# Esquematico_fonte_3_3V.net
KiCad netlist of a schematic drawn in Altium Designer
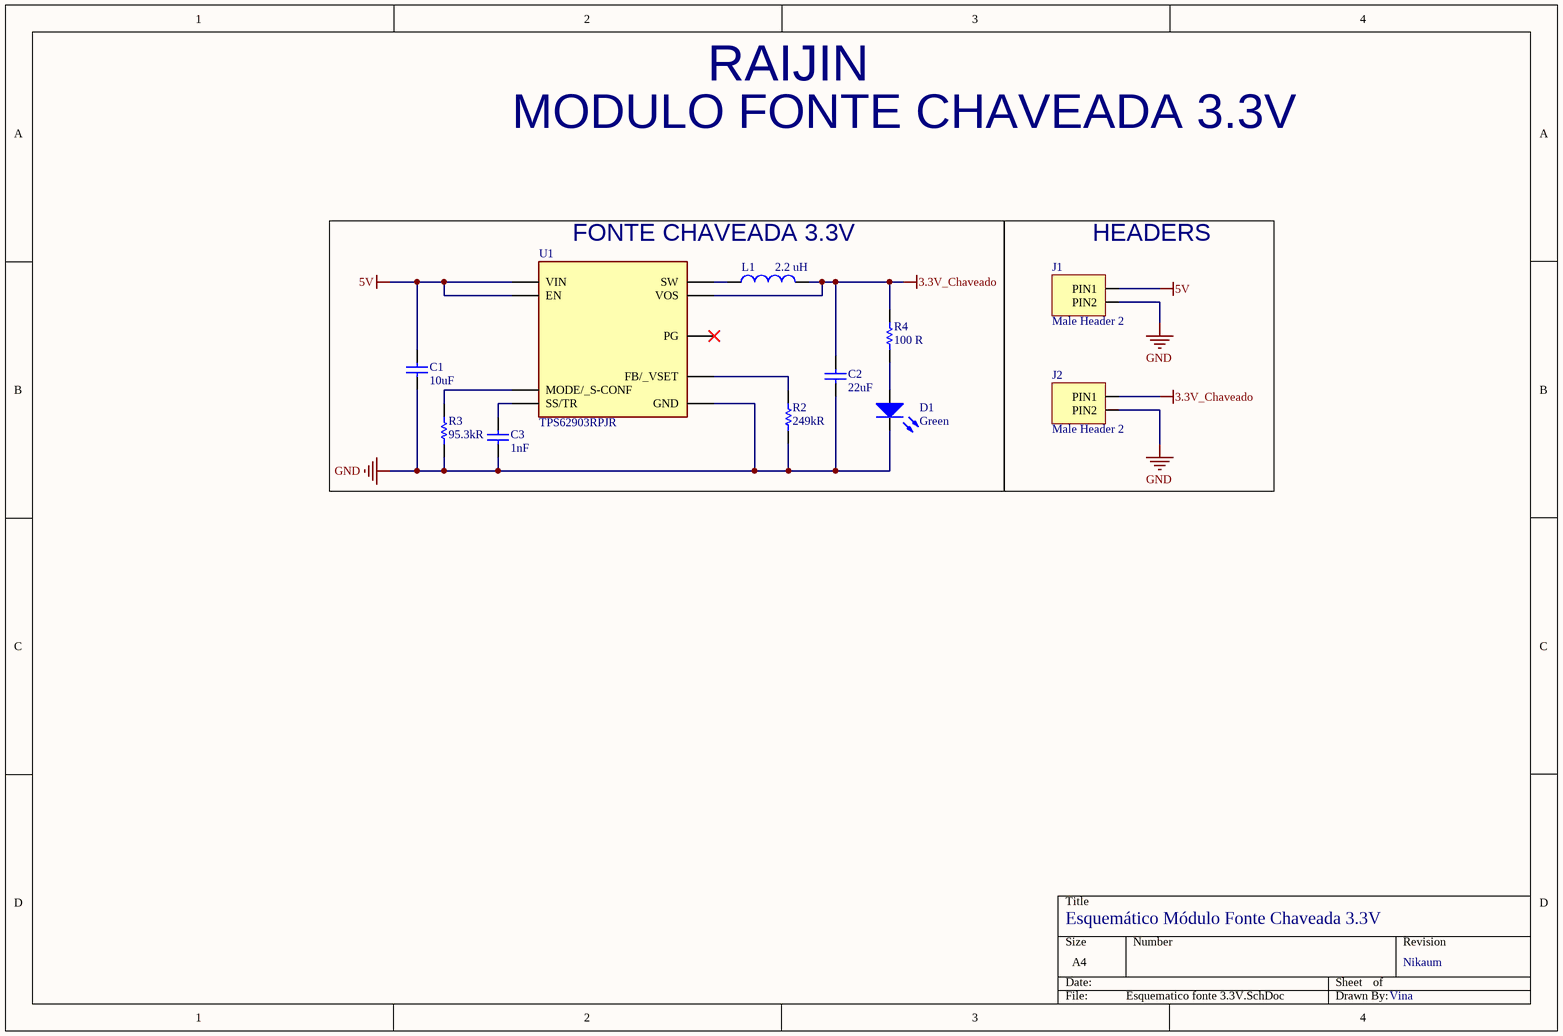
[diagram p0: Esquematico fonte 3.3V.SchDoc]

(export (version "E")
  (design (tool "Eeschema 10.0.6"))
  (components
    (comp (ref "C1")
      (value "10uF")
      (footprint "C0805")
      (description "CAP CER 10uF 10V 10% X5R 0805")
      (fields
        (field (name "MANUFACTURER") "KEMET")
        (field (name "PART NUMBER") "C0805C106K8PACTU")
        (field (name "LIBRARY CONTROL - PERSON THAT DID THE LAST UPDATE FOOTPRINT") "Marcos")
        (field (name "LIBRARY CONTROL - PERSON THAT DID THE LAST UPDATE SCHEMATIC") "Marcos")
      )
      (libsource (lib "Uai!Tecas") (part "C0805C106K8PACTU"))
    )
    (comp (ref "C2")
      (value "22uF")
      (footprint "C0603")
      (description "CAP TAN 22uF 6.3V 0603")
      (fields
        (field (name "MANUFACTURER") "AVX")
        (field (name "PART NUMBER") "F980J226MMA")
        (field (name "LIBRARY CONTROL - PERSON THAT CHECKED FOOTPRINT") "Nikaum")
        (field (name "LIBRARY CONTROL - PERSON THAT CHECKED SCHEMATIC") "Nikaum")
        (field (name "LIBRARY CONTROL - PERSON THAT DID THE LAST UPDATE FOOTPRINT") "Nikaum")
        (field (name "LIBRARY CONTROL - PERSON THAT DID THE LAST UPDATE SCHEMATIC") "Nikaum")
      )
      (libsource (lib "Uai!Tecas") (part "F980J226MMA"))
    )
    (comp (ref "C3")
      (value "1nF")
      (footprint "C0402")
      (description "CAP CER 1nF 10V 10% X5R 0402")
      (fields
        (field (name "MANUFACTURER") "Murata")
        (field (name "PART NUMBER") "GRM155R61A102KA01D")
        (field (name "LIBRARY CONTROL - PERSON THAT DID THE LAST UPDATE FOOTPRINT") "Marcos")
        (field (name "LIBRARY CONTROL - PERSON THAT DID THE LAST UPDATE SCHEMATIC") "Marcos")
      )
      (libsource (lib "Uai!Tecas") (part "GRM155R61A102KA01D"))
    )
    (comp (ref "D1")
      (value "Green")
      (footprint "LED_0603")
      (description "LED 0.072W GREEN 40MCD 0603")
      (fields
        (field (name "MANUFACTURER") "Wurth Elektronik")
        (field (name "PART NUMBER") "150060VS75000")
        (field (name "LIBRARY CONTROL - PERSON THAT CHECKED FOOTPRINT") "Stéfany (Ster)")
        (field (name "LIBRARY CONTROL - PERSON THAT CHECKED SCHEMATIC") "Stéfany (Ster)")
        (field (name "LIBRARY CONTROL - PERSON THAT DID THE LAST UPDATE FOOTPRINT") "Stéfany (Ster)")
        (field (name "LIBRARY CONTROL - PERSON THAT DID THE LAST UPDATE SCHEMATIC") "Marcos")
      )
      (libsource (lib "Uai!Tecas") (part "150060VS75000"))
    )
    (comp (ref "J1")
      (value "Male Header 2")
      (footprint "MALE HEADER 2")
      (fields
        (field (name "LIBRARY CONTROL - PERSON THAT DID THE LAST UPDATE SCHEMATIC") "Marcos")
        (field (name "LIBRARY CONTROL - PERSONT THAT DID THE LAST UPDATE FOOTPRINT") "Marcos")
      )
      (libsource (lib "Header") (part "Male Header 2"))
    )
    (comp (ref "J2")
      (value "Male Header 2")
      (footprint "MALE HEADER 2")
      (fields
        (field (name "LIBRARY CONTROL - PERSON THAT DID THE LAST UPDATE SCHEMATIC") "Marcos")
        (field (name "LIBRARY CONTROL - PERSONT THAT DID THE LAST UPDATE FOOTPRINT") "Marcos")
      )
      (libsource (lib "Header") (part "Male Header 2"))
    )
    (comp (ref "L1")
      (value "2.2 uH")
      (footprint "XAL0402")
      (description "IND FIX 2.2uH Shld 20% 5.5A 38.7mOhms AECQ2")
      (fields
        (field (name "MANUFACTURER") "Coilcraft")
        (field (name "PART NUMBER") "XAL5030-332MEB")
        (field (name "LIBRARY CONTROL - PERSON THAT CHECKED FOOTPRINT") "Nikaum")
        (field (name "LIBRARY CONTROL - PERSON THAT CHECKED SCHEMATIC") "Nikaum")
      )
      (libsource (lib "Uai!Tecas") (part "XAL4020-222MEB"))
    )
    (comp (ref "R2")
      (value "249kR")
      (footprint "RESISTOR_0805")
      (description "RES SMD 249K OHM 1% 1/8W 0805")
      (fields
        (field (name "MANUFACTURER") "Vishay / Dale")
        (field (name "PART NUMBER") "CRCW0805249KFKEA")
        (field (name "LIBRARY CONTROL - PERSON THAT CHECKED SCHEMATIC") "Marcos")
        (field (name "LIBRARY CONTROL - PERSON THAT DID THE LAST UPDATE FOOTPRINT") "Dalarme")
        (field (name "LIBRARY CONTROL - PERSON THAT DID THE LAST UPDATE SCHEMATIC") "Marcos")
      )
      (libsource (lib "Uai!Tecas") (part "CRCW0805249KFKEA"))
    )
    (comp (ref "R3")
      (value "95.3kR")
      (footprint "RESISTOR_0402")
      (description "RES SMD 95.3K OHM 1% 1/16W 0402")
      (fields
        (field (name "MANUFACTURER") "Vishay")
        (field (name "PART NUMBER") "CRCW040295K3FKED")
        (field (name "LIBRARY CONTROL - PERSON THAT DID THE LAST UPDATE SCHEMATIC") "Marcos")
        (field (name "LIBRARY CONTROL - PERSON THAT DID THE LAST UPDATE FOOTPRINT") "Marcos")
      )
      (libsource (lib "Uai!Tecas") (part "CRCW040295K3FKED"))
    )
    (comp (ref "R4")
      (value "100 R")
      (footprint "RESISTOR_0603")
      (description "RES SMD 100 OHM 1% 1/10W 0603")
      (fields
        (field (name "MANUFACTURER") "Yageo")
        (field (name "PART NUMBER") "RC0603FR-10100RL")
        (field (name "LIBRARY CONTROL - PERSON THAT CHECKED FOOTPRINT") "Nikaum")
        (field (name "LIBRARY CONTROL - PERSON THAT CHECKED SCHEMATIC") "Nikaum")
        (field (name "LIBRARY CONTROL - PERSON THAT DID THE LAST UPDATE FOOTPRINT") "Nicolas")
        (field (name "LIBRARY CONTROL - PERSON THAT DID THE LAST UPDATE SCHEMATIC") "Nikaum")
      )
      (libsource (lib "Uai!Tecas") (part "RC0603FR-10100RL"))
    )
    (comp (ref "U1")
      (value "TPS62903RPJR")
      (footprint "VQFN-HR-9")
      (description "IC REG SWITCHING 3A 0.4V to 5.5V")
      (fields
        (field (name "MANUFACTURER") "Texas Instruments")
        (field (name "LIBRARY CONTROL - PERSON THAT DID THE LAST UPDATE FOOTPRINT") "Marcos")
        (field (name "LIBRARY CONTROL - PERSON THAT DID THE LAST UPDATE SCHEMATIC") "Marcos")
      )
      (libsource (lib "Voltage Regulator") (part "TPS62903RPJR"))
    )
  )
  (nets
    (net (code "1") (name "3.3V_Chaveado") (class "Default")
      (node (ref "C2") (pin "2") (pinfunction "2_2") (pintype "passive"))
      (node (ref "J2") (pin "PIN1") (pinfunction "PIN1_PIN1") (pintype "passive"))
      (node (ref "L1") (pin "2") (pinfunction "2_2") (pintype "passive"))
      (node (ref "R4") (pin "2") (pinfunction "2_2") (pintype "passive"))
      (node (ref "U1") (pin "VOS") (pinfunction "VOS_VOS") (pintype "passive"))
    )
    (net (code "2") (name "5V") (class "Default")
      (node (ref "C1") (pin "2") (pinfunction "2_2") (pintype "passive"))
      (node (ref "J1") (pin "PIN1") (pinfunction "PIN1_PIN1") (pintype "passive"))
      (node (ref "U1") (pin "EN") (pinfunction "EN_EN") (pintype "passive"))
      (node (ref "U1") (pin "VIN") (pinfunction "VIN_VIN") (pintype "passive"))
    )
    (net (code "3") (name "GND") (class "Default")
      (node (ref "C1") (pin "1") (pinfunction "1_1") (pintype "passive"))
      (node (ref "C2") (pin "1") (pinfunction "1_1") (pintype "passive"))
      (node (ref "C3") (pin "1") (pinfunction "1_1") (pintype "passive"))
      (node (ref "D1") (pin "C") (pinfunction "C_C") (pintype "passive"))
      (node (ref "J1") (pin "PIN2") (pinfunction "PIN2_PIN2") (pintype "passive"))
      (node (ref "J2") (pin "PIN2") (pinfunction "PIN2_PIN2") (pintype "passive"))
      (node (ref "R2") (pin "1") (pinfunction "1_1") (pintype "passive"))
      (node (ref "R3") (pin "1") (pinfunction "1_1") (pintype "passive"))
      (node (ref "U1") (pin "GND") (pinfunction "GND_GND") (pintype "passive"))
    )
    (net (code "4") (name "Net-(D1-PadA)") (class "Default")
      (node (ref "D1") (pin "A") (pinfunction "A_A") (pintype "passive"))
      (node (ref "R4") (pin "1") (pinfunction "1_1") (pintype "passive"))
    )
    (net (code "5") (name "Net-(L1-Pad1)") (class "Default")
      (node (ref "L1") (pin "1") (pinfunction "1_1") (pintype "passive"))
      (node (ref "U1") (pin "SW") (pinfunction "SW_SW") (pintype "passive"))
    )
    (net (code "6") (name "Net-(U1-FB{slash}_VSET)") (class "Default")
      (node (ref "R2") (pin "2") (pinfunction "2_2") (pintype "passive"))
      (node (ref "U1") (pin "FB") (pinfunction "FB/_VSET_FB") (pintype "passive"))
    )
    (net (code "7") (name "Net-(U1-MODE{slash}_S-CONF)") (class "Default")
      (node (ref "R3") (pin "2") (pinfunction "2_2") (pintype "passive"))
      (node (ref "U1") (pin "MODE") (pinfunction "MODE/_S-CONF_MODE") (pintype "passive"))
    )
    (net (code "8") (name "Net-(U1-SS{slash}TR)") (class "Default")
      (node (ref "C3") (pin "2") (pinfunction "2_2") (pintype "passive"))
      (node (ref "U1") (pin "SS") (pinfunction "SS/TR_SS") (pintype "passive"))
    )
    (net (code "9") (name "unconnected-(U1-PadPG)") (class "Default")
      (node (ref "U1") (pin "PG") (pinfunction "PG_PG") (pintype "passive+no_connect"))
    )
  )
)
